# rev11.net
KiCad netlist of a schematic drawn in EAGLE
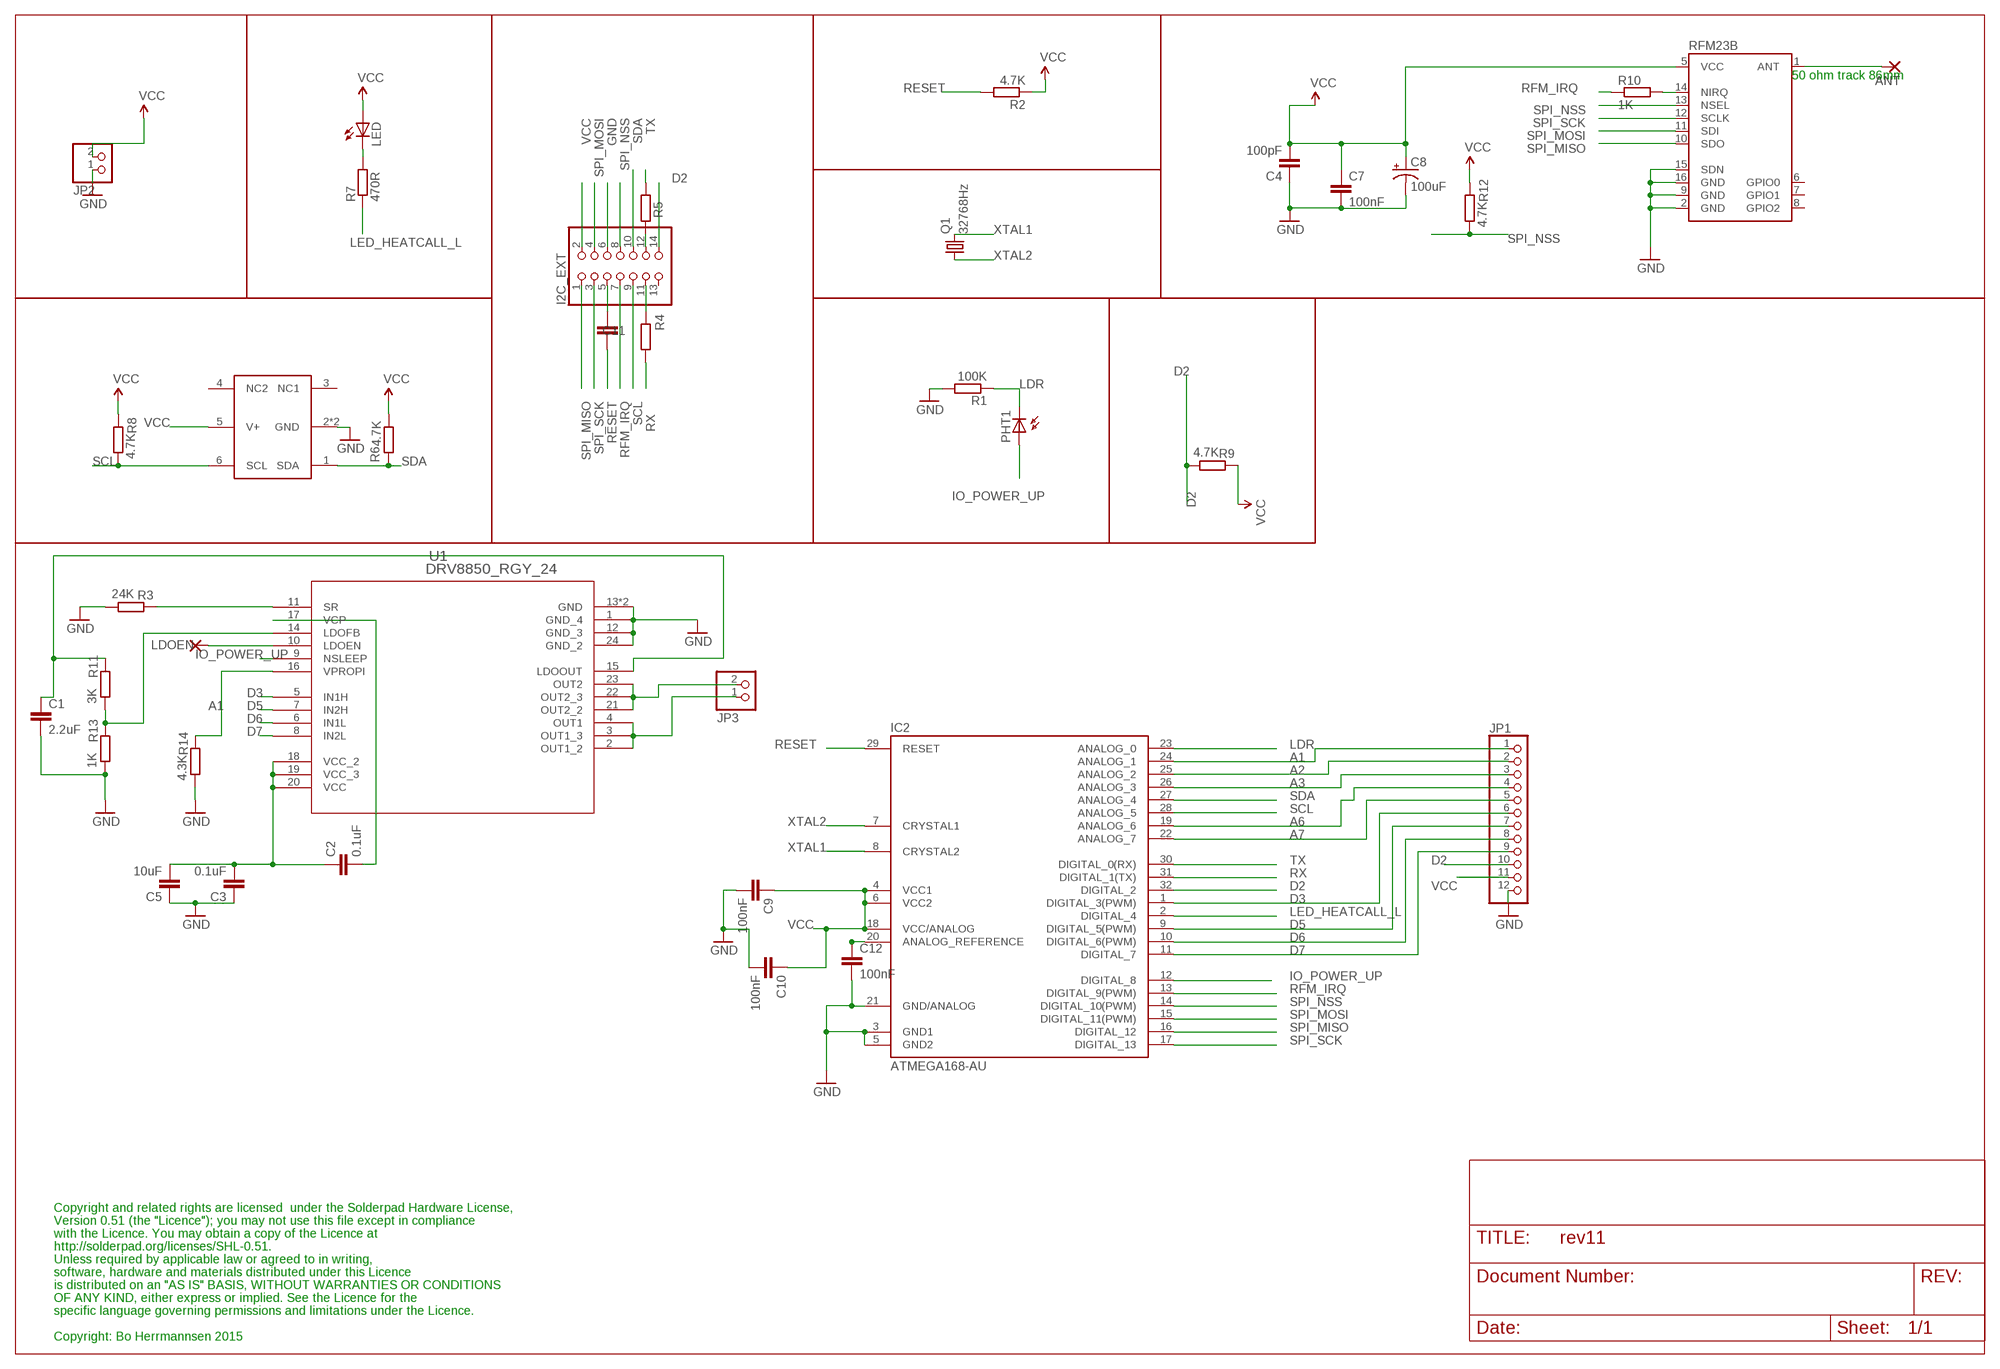
[diagram p0: schematic, sheet 1]

(export (version "E")
  (design (tool "Eeschema 10.0.6"))
  (components
    (comp (ref "ANT")
      (value "SMD2")
      (footprint "eagle-import:SMD1,27-2,54")
      (libsource (lib "eagle-import") (part "SMD2"))
    )
    (comp (ref "C1")
      (value "2.2uF")
      (footprint "eagle-import:C0603")
      (libsource (lib "eagle-import") (part "C-EUC0603"))
    )
    (comp (ref "C2")
      (value "0.1uF")
      (footprint "eagle-import:C0603")
      (libsource (lib "eagle-import") (part "C-EUC0603"))
    )
    (comp (ref "C3")
      (value "0.1uF")
      (footprint "eagle-import:C0603")
      (libsource (lib "eagle-import") (part "C-EUC0603"))
    )
    (comp (ref "C4")
      (value "100pF")
      (footprint "eagle-import:C0603")
      (libsource (lib "eagle-import") (part "C-EUC0603"))
    )
    (comp (ref "C5")
      (value "10uF")
      (footprint "eagle-import:C0603")
      (libsource (lib "eagle-import") (part "C-EUC0603"))
    )
    (comp (ref "C7")
      (value "100nF")
      (footprint "eagle-import:C0603")
      (libsource (lib "eagle-import") (part "C-EUC0603"))
    )
    (comp (ref "C8")
      (value "100uF")
      (footprint "eagle-import:EIA3216")
      (libsource (lib "eagle-import") (part "CAP_POL1206"))
    )
    (comp (ref "C9")
      (value "100nF")
      (footprint "eagle-import:C0603")
      (libsource (lib "eagle-import") (part "C-EUC0603"))
    )
    (comp (ref "C10")
      (value "100nF")
      (footprint "eagle-import:C0603")
      (libsource (lib "eagle-import") (part "C-EUC0603"))
    )
    (comp (ref "C11")
      (value "100nF")
      (footprint "eagle-import:C0603")
      (libsource (lib "eagle-import") (part "C-EUC0603"))
    )
    (comp (ref "C12")
      (value "100nF")
      (footprint "eagle-import:C0603")
      (libsource (lib "eagle-import") (part "C-EUC0603"))
    )
    (comp (ref "I2C_EXT")
      (value "PINHD-2X7")
      (footprint "eagle-import:2X07")
      (libsource (lib "eagle-import") (part "PINHD-2X7"))
    )
    (comp (ref "IC2")
      (value "ATMEGA168-AU")
      (footprint "eagle-import:TQFP32-08")
      (libsource (lib "eagle-import") (part "ATMEGA168-AU"))
    )
    (comp (ref "JP1")
      (value "PINHD-1X12")
      (footprint "eagle-import:1X12")
      (libsource (lib "eagle-import") (part "PINHD-1X12"))
    )
    (comp (ref "JP2")
      (value "PINHD-1X2")
      (footprint "eagle-import:1X02")
      (libsource (lib "eagle-import") (part "PINHD-1X2"))
    )
    (comp (ref "JP3")
      (value "PINHD-1X2")
      (footprint "eagle-import:1X02")
      (libsource (lib "eagle-import") (part "PINHD-1X2"))
    )
    (comp (ref "LDOEN")
      (value "WIREPAD2,15/1,0")
      (footprint "eagle-import:2,15_1,0")
      (libsource (lib "eagle-import") (part "WIREPAD2,15/1,0"))
    )
    (comp (ref "LED")
      (value "LEDCHIPLED_0603")
      (footprint "eagle-import:CHIPLED_0603")
      (libsource (lib "eagle-import") (part "LEDCHIPLED_0603"))
    )
    (comp (ref "PHT1")
      (value "BPX65")
      (footprint "eagle-import:BPX65")
      (fields (field (name "MPN") "BPX65."))
      (libsource (lib "eagle-import") (part "BPX65"))
    )
    (comp (ref "Q1")
      (value "32768Hz")
      (footprint "eagle-import:MC-306")
      (fields (field (name "MPN") "MC-306 60.0KHZ  100PPM ,12.5PF"))
      (libsource (lib "eagle-import") (part "MC-306"))
    )
    (comp (ref "R1")
      (value "100K")
      (footprint "eagle-import:R0603")
      (libsource (lib "eagle-import") (part "R-EU_R0603"))
    )
    (comp (ref "R2")
      (value "4.7K")
      (footprint "eagle-import:R0603")
      (libsource (lib "eagle-import") (part "R-EU_R0603"))
    )
    (comp (ref "R3")
      (value "24K")
      (footprint "eagle-import:R0603")
      (libsource (lib "eagle-import") (part "R-EU_R0603"))
    )
    (comp (ref "R4")
      (value "4.7K")
      (footprint "eagle-import:R0603")
      (libsource (lib "eagle-import") (part "R-EU_R0603"))
    )
    (comp (ref "R5")
      (value "4.7K")
      (footprint "eagle-import:R0603")
      (libsource (lib "eagle-import") (part "R-EU_R0603"))
    )
    (comp (ref "R6")
      (value "4.7K")
      (footprint "eagle-import:R0603")
      (libsource (lib "eagle-import") (part "R-EU_R0603"))
    )
    (comp (ref "R7")
      (value "470R")
      (footprint "eagle-import:R0603")
      (libsource (lib "eagle-import") (part "R-EU_R0603"))
    )
    (comp (ref "R8")
      (value "4.7K")
      (footprint "eagle-import:R0603")
      (libsource (lib "eagle-import") (part "R-EU_R0603"))
    )
    (comp (ref "R9")
      (value "4.7K")
      (footprint "eagle-import:R0603")
      (libsource (lib "eagle-import") (part "R-EU_R0603"))
    )
    (comp (ref "R10")
      (value "1K")
      (footprint "eagle-import:R0603")
      (libsource (lib "eagle-import") (part "R-EU_R0603"))
    )
    (comp (ref "R11")
      (value "3K")
      (footprint "eagle-import:R0603")
      (libsource (lib "eagle-import") (part "R-EU_R0603"))
    )
    (comp (ref "R12")
      (value "4.7K")
      (footprint "eagle-import:R0603")
      (libsource (lib "eagle-import") (part "R-EU_R0603"))
    )
    (comp (ref "R13")
      (value "1K")
      (footprint "eagle-import:R0603")
      (libsource (lib "eagle-import") (part "R-EU_R0603"))
    )
    (comp (ref "R14")
      (value "4.3K")
      (footprint "eagle-import:R0603")
      (libsource (lib "eagle-import") (part "R-EU_R0603"))
    )
    (comp (ref "RFM23B")
      (value "RFM23B")
      (footprint "eagle-import:RFM23-XXX-S1")
      (libsource (lib "eagle-import") (part "RFM23B"))
    )
    (comp (ref "U$4")
      (value "SHT21")
      (footprint "eagle-import:SHT21")
      (libsource (lib "eagle-import") (part "SHT21"))
    )
    (comp (ref "U1")
      (value "DRV8850_RGY_24")
      (footprint "eagle-import:RGY_24")
      (fields (field (name "MANUFACTURER_PART_NUMBER") "drv8850_rgy_24"))
      (libsource (lib "eagle-import") (part "DRV8850_RGY_24"))
    )
  )
  (nets
    (net (code "1") (name "/A1") (class "Default")
      (node (ref "IC2") (pin "24") (pinfunction "ANALOG_1_24") (pintype "bidirectional"))
      (node (ref "JP1") (pin "1") (pinfunction "1_1") (pintype "passive"))
      (node (ref "R14") (pin "2") (pinfunction "2_2") (pintype "passive"))
      (node (ref "U1") (pin "16") (pinfunction "VPROPI_16") (pintype "output"))
    )
    (net (code "2") (name "/A2") (class "Default")
      (node (ref "IC2") (pin "25") (pinfunction "ANALOG_2_25") (pintype "bidirectional"))
      (node (ref "JP1") (pin "2") (pinfunction "2_2") (pintype "passive"))
    )
    (net (code "3") (name "/A3") (class "Default")
      (node (ref "IC2") (pin "26") (pinfunction "ANALOG_3_26") (pintype "bidirectional"))
      (node (ref "JP1") (pin "3") (pinfunction "3_3") (pintype "passive"))
    )
    (net (code "4") (name "/A6") (class "Default")
      (node (ref "IC2") (pin "19") (pinfunction "ANALOG_6_19") (pintype "passive"))
      (node (ref "JP1") (pin "4") (pinfunction "4_4") (pintype "passive"))
    )
    (net (code "5") (name "/A7") (class "Default")
      (node (ref "IC2") (pin "22") (pinfunction "ANALOG_7_22") (pintype "passive"))
      (node (ref "JP1") (pin "5") (pinfunction "5_5") (pintype "passive"))
    )
    (net (code "6") (name "/D2") (class "Default")
      (node (ref "I2C_EXT") (pin "14") (pinfunction "14_14") (pintype "passive"))
      (node (ref "IC2") (pin "32") (pinfunction "DIGITAL_2_32") (pintype "bidirectional"))
      (node (ref "JP1") (pin "10") (pinfunction "10_10") (pintype "passive"))
      (node (ref "R9") (pin "1") (pinfunction "1_1") (pintype "passive"))
    )
    (net (code "7") (name "/D3") (class "Default")
      (node (ref "IC2") (pin "1") (pinfunction "DIGITAL_3(PWM)_1") (pintype "bidirectional"))
      (node (ref "JP1") (pin "6") (pinfunction "6_6") (pintype "passive"))
      (node (ref "U1") (pin "5") (pinfunction "IN1H_5") (pintype "input"))
    )
    (net (code "8") (name "/D5") (class "Default")
      (node (ref "IC2") (pin "9") (pinfunction "DIGITAL_5(PWM)_9") (pintype "bidirectional"))
      (node (ref "JP1") (pin "7") (pinfunction "7_7") (pintype "passive"))
      (node (ref "U1") (pin "7") (pinfunction "IN2H_7") (pintype "input"))
    )
    (net (code "9") (name "/D6") (class "Default")
      (node (ref "IC2") (pin "10") (pinfunction "DIGITAL_6(PWM)_10") (pintype "bidirectional"))
      (node (ref "JP1") (pin "8") (pinfunction "8_8") (pintype "passive"))
      (node (ref "U1") (pin "6") (pinfunction "IN1L_6") (pintype "input"))
    )
    (net (code "10") (name "/D7") (class "Default")
      (node (ref "IC2") (pin "11") (pinfunction "DIGITAL_7_11") (pintype "bidirectional"))
      (node (ref "JP1") (pin "9") (pinfunction "9_9") (pintype "passive"))
      (node (ref "U1") (pin "8") (pinfunction "IN2L_8") (pintype "input"))
    )
    (net (code "11") (name "/IO_POWER_UP") (class "Default")
      (node (ref "IC2") (pin "12") (pinfunction "DIGITAL_8_12") (pintype "bidirectional"))
      (node (ref "PHT1") (pin "A") (pinfunction "A_A") (pintype "passive"))
      (node (ref "U1") (pin "9") (pinfunction "NSLEEP_9") (pintype "input"))
    )
    (net (code "12") (name "/LDR") (class "Default")
      (node (ref "IC2") (pin "23") (pinfunction "ANALOG_0_23") (pintype "bidirectional"))
      (node (ref "PHT1") (pin "K") (pinfunction "C_K") (pintype "passive"))
      (node (ref "R1") (pin "1") (pinfunction "1_1") (pintype "passive"))
    )
    (net (code "13") (name "/LED_HEATCALL_L") (class "Default")
      (node (ref "IC2") (pin "2") (pinfunction "DIGITAL_4_2") (pintype "bidirectional"))
      (node (ref "R7") (pin "1") (pinfunction "1_1") (pintype "passive"))
    )
    (net (code "14") (name "/RESET") (class "Default")
      (node (ref "C11") (pin "1") (pinfunction "1_1") (pintype "passive"))
      (node (ref "IC2") (pin "29") (pinfunction "RESET_29") (pintype "bidirectional"))
      (node (ref "R2") (pin "2") (pinfunction "2_2") (pintype "passive"))
    )
    (net (code "15") (name "/RFM_IRQ") (class "Default")
      (node (ref "I2C_EXT") (pin "7") (pinfunction "7_7") (pintype "passive"))
      (node (ref "IC2") (pin "13") (pinfunction "DIGITAL_9(PWM)_13") (pintype "bidirectional"))
      (node (ref "R10") (pin "1") (pinfunction "1_1") (pintype "passive"))
    )
    (net (code "16") (name "/RX") (class "Default")
      (node (ref "IC2") (pin "31") (pinfunction "DIGITAL_1(TX)_31") (pintype "bidirectional"))
      (node (ref "R4") (pin "1") (pinfunction "1_1") (pintype "passive"))
    )
    (net (code "17") (name "/SCL") (class "Default")
      (node (ref "I2C_EXT") (pin "9") (pinfunction "9_9") (pintype "passive"))
      (node (ref "IC2") (pin "28") (pinfunction "ANALOG_5_28") (pintype "bidirectional"))
      (node (ref "R8") (pin "1") (pinfunction "1_1") (pintype "passive"))
      (node (ref "U$4") (pin "6") (pinfunction "SCL_6") (pintype "bidirectional"))
    )
    (net (code "18") (name "/SDA") (class "Default")
      (node (ref "I2C_EXT") (pin "10") (pinfunction "10_10") (pintype "passive"))
      (node (ref "IC2") (pin "27") (pinfunction "ANALOG_4_27") (pintype "bidirectional"))
      (node (ref "R6") (pin "2") (pinfunction "2_2") (pintype "passive"))
      (node (ref "U$4") (pin "1") (pinfunction "SDA_1") (pintype "bidirectional"))
    )
    (net (code "19") (name "/SPI_MISO") (class "Default")
      (node (ref "I2C_EXT") (pin "1") (pinfunction "1_1") (pintype "passive"))
      (node (ref "IC2") (pin "16") (pinfunction "DIGITAL_12_16") (pintype "bidirectional"))
      (node (ref "RFM23B") (pin "10") (pinfunction "SDO_10") (pintype "output"))
    )
    (net (code "20") (name "/SPI_MOSI") (class "Default")
      (node (ref "I2C_EXT") (pin "4") (pinfunction "4_4") (pintype "passive"))
      (node (ref "IC2") (pin "15") (pinfunction "DIGITAL_11(PWM)_15") (pintype "bidirectional"))
      (node (ref "RFM23B") (pin "11") (pinfunction "SDI_11") (pintype "input"))
    )
    (net (code "21") (name "/SPI_NSS") (class "Default")
      (node (ref "I2C_EXT") (pin "8") (pinfunction "8_8") (pintype "passive"))
      (node (ref "IC2") (pin "14") (pinfunction "DIGITAL_10(PWM)_14") (pintype "bidirectional"))
      (node (ref "R12") (pin "1") (pinfunction "1_1") (pintype "passive"))
      (node (ref "RFM23B") (pin "13") (pinfunction "NSEL_13") (pintype "input"))
    )
    (net (code "22") (name "/SPI_SCK") (class "Default")
      (node (ref "I2C_EXT") (pin "3") (pinfunction "3_3") (pintype "passive"))
      (node (ref "IC2") (pin "17") (pinfunction "DIGITAL_13_17") (pintype "bidirectional"))
      (node (ref "RFM23B") (pin "12") (pinfunction "SCLK_12") (pintype "input"))
    )
    (net (code "23") (name "/TX") (class "Default")
      (node (ref "IC2") (pin "30") (pinfunction "DIGITAL_0(RX)_30") (pintype "bidirectional"))
      (node (ref "R5") (pin "1") (pinfunction "1_1") (pintype "passive"))
    )
    (net (code "24") (name "/XTAL1") (class "Default")
      (node (ref "IC2") (pin "8") (pinfunction "CRYSTAL2_8") (pintype "bidirectional"))
      (node (ref "Q1") (pin "4") (pinfunction "2_4") (pintype "passive"))
    )
    (net (code "25") (name "/XTAL2") (class "Default")
      (node (ref "IC2") (pin "7") (pinfunction "CRYSTAL1_7") (pintype "bidirectional"))
      (node (ref "Q1") (pin "1") (pinfunction "1_1") (pintype "passive"))
    )
    (net (code "26") (name "GND") (class "Default")
      (node (ref "C1") (pin "2") (pinfunction "2_2") (pintype "passive"))
      (node (ref "C10") (pin "2") (pinfunction "2_2") (pintype "passive"))
      (node (ref "C12") (pin "2") (pinfunction "2_2") (pintype "passive"))
      (node (ref "C3") (pin "1") (pinfunction "1_1") (pintype "passive"))
      (node (ref "C4") (pin "1") (pinfunction "1_1") (pintype "passive"))
      (node (ref "C5") (pin "1") (pinfunction "1_1") (pintype "passive"))
      (node (ref "C7") (pin "2") (pinfunction "2_2") (pintype "passive"))
      (node (ref "C8") (pin "C") (pinfunction "-_C") (pintype "passive"))
      (node (ref "C9") (pin "2") (pinfunction "2_2") (pintype "passive"))
      (node (ref "I2C_EXT") (pin "6") (pinfunction "6_6") (pintype "passive"))
      (node (ref "IC2") (pin "21") (pinfunction "GND/ANALOG_21") (pintype "power_in"))
      (node (ref "IC2") (pin "3") (pinfunction "GND1_3") (pintype "power_in"))
      (node (ref "IC2") (pin "5") (pinfunction "GND2_5") (pintype "power_in"))
      (node (ref "JP1") (pin "12") (pinfunction "12_12") (pintype "passive"))
      (node (ref "JP2") (pin "1") (pinfunction "1_1") (pintype "passive"))
      (node (ref "R1") (pin "2") (pinfunction "2_2") (pintype "passive"))
      (node (ref "R13") (pin "1") (pinfunction "1_1") (pintype "passive"))
      (node (ref "R14") (pin "1") (pinfunction "1_1") (pintype "passive"))
      (node (ref "R3") (pin "1") (pinfunction "1_1") (pintype "passive"))
      (node (ref "RFM23B") (pin "15") (pinfunction "SDN_15") (pintype "input"))
      (node (ref "RFM23B") (pin "16") (pinfunction "GND_16") (pintype "power_in"))
      (node (ref "RFM23B") (pin "2") (pinfunction "GND_2") (pintype "power_in"))
      (node (ref "RFM23B") (pin "9") (pinfunction "GND_9") (pintype "power_in"))
      (node (ref "U$4") (pin "2") (pinfunction "GND_2") (pintype "bidirectional"))
      (node (ref "U$4") (pin "P$1") (pinfunction "GND_P$1") (pintype "bidirectional"))
      (node (ref "U1") (pin "1") (pinfunction "GND_4_1") (pintype "power_in"))
      (node (ref "U1") (pin "12") (pinfunction "GND_3_12") (pintype "power_in"))
      (node (ref "U1") (pin "13") (pinfunction "GND_13") (pintype "power_in"))
      (node (ref "U1") (pin "24") (pinfunction "GND_2_24") (pintype "power_in"))
      (node (ref "U1") (pin "25") (pinfunction "GND_25") (pintype "power_in"))
    )
    (net (code "27") (name "Net-(ANT-P)") (class "Default")
      (node (ref "ANT") (pin "1") (pinfunction "P_1") (pintype "passive"))
      (node (ref "RFM23B") (pin "1") (pinfunction "ANT_1") (pintype "bidirectional"))
    )
    (net (code "28") (name "Net-(C11-Pad2)") (class "Default")
      (node (ref "C11") (pin "2") (pinfunction "2_2") (pintype "passive"))
      (node (ref "I2C_EXT") (pin "5") (pinfunction "5_5") (pintype "passive"))
    )
    (net (code "29") (name "Net-(I2C_EXT-Pad11)") (class "Default")
      (node (ref "I2C_EXT") (pin "11") (pinfunction "11_11") (pintype "passive"))
      (node (ref "R4") (pin "2") (pinfunction "2_2") (pintype "passive"))
    )
    (net (code "30") (name "Net-(I2C_EXT-Pad12)") (class "Default")
      (node (ref "I2C_EXT") (pin "12") (pinfunction "12_12") (pintype "passive"))
      (node (ref "R5") (pin "2") (pinfunction "2_2") (pintype "passive"))
    )
    (net (code "31") (name "Net-(IC2-ANALOG_REFERENCE)") (class "Default")
      (node (ref "C12") (pin "1") (pinfunction "1_1") (pintype "passive"))
      (node (ref "IC2") (pin "20") (pinfunction "ANALOG_REFERENCE_20") (pintype "passive"))
    )
    (net (code "32") (name "Net-(LDOEN-P)") (class "Default")
      (node (ref "LDOEN") (pin "1") (pinfunction "P_1") (pintype "passive"))
      (node (ref "U1") (pin "10") (pinfunction "LDOEN_10") (pintype "input"))
    )
    (net (code "33") (name "Net-(LED-PadC)") (class "Default")
      (node (ref "LED") (pin "C") (pinfunction "C_C") (pintype "passive"))
      (node (ref "R7") (pin "2") (pinfunction "2_2") (pintype "passive"))
    )
    (net (code "34") (name "Net-(RFM23B-NIRQ)") (class "Default")
      (node (ref "R10") (pin "2") (pinfunction "2_2") (pintype "passive"))
      (node (ref "RFM23B") (pin "14") (pinfunction "NIRQ_14") (pintype "output"))
    )
    (net (code "35") (name "Net-(U1-LDOFB)") (class "Default")
      (node (ref "R11") (pin "1") (pinfunction "1_1") (pintype "passive"))
      (node (ref "R13") (pin "2") (pinfunction "2_2") (pintype "passive"))
      (node (ref "U1") (pin "14") (pinfunction "LDOFB_14") (pintype "input"))
    )
    (net (code "36") (name "Net-(U1-LDOOUT)") (class "Default")
      (node (ref "C1") (pin "1") (pinfunction "1_1") (pintype "passive"))
      (node (ref "R11") (pin "2") (pinfunction "2_2") (pintype "passive"))
      (node (ref "U1") (pin "15") (pinfunction "LDOOUT_15") (pintype "output"))
    )
    (net (code "37") (name "Net-(U1-OUT1)") (class "Default")
      (node (ref "JP3") (pin "1") (pinfunction "1_1") (pintype "passive"))
      (node (ref "U1") (pin "2") (pinfunction "OUT1_2_2") (pintype "output"))
      (node (ref "U1") (pin "3") (pinfunction "OUT1_3_3") (pintype "output"))
      (node (ref "U1") (pin "4") (pinfunction "OUT1_4") (pintype "output"))
    )
    (net (code "38") (name "Net-(U1-OUT2)") (class "Default")
      (node (ref "JP3") (pin "2") (pinfunction "2_2") (pintype "passive"))
      (node (ref "U1") (pin "21") (pinfunction "OUT2_2_21") (pintype "output"))
      (node (ref "U1") (pin "22") (pinfunction "OUT2_3_22") (pintype "output"))
      (node (ref "U1") (pin "23") (pinfunction "OUT2_23") (pintype "output"))
    )
    (net (code "39") (name "Net-(U1-SR)") (class "Default")
      (node (ref "R3") (pin "2") (pinfunction "2_2") (pintype "passive"))
      (node (ref "U1") (pin "11") (pinfunction "SR_11") (pintype "bidirectional"))
    )
    (net (code "40") (name "Net-(U1-VCP)") (class "Default")
      (node (ref "C2") (pin "2") (pinfunction "2_2") (pintype "passive"))
      (node (ref "U1") (pin "17") (pinfunction "VCP_17") (pintype "passive"))
    )
    (net (code "41") (name "VCC") (class "Default")
      (node (ref "C10") (pin "1") (pinfunction "1_1") (pintype "passive"))
      (node (ref "C2") (pin "1") (pinfunction "1_1") (pintype "passive"))
      (node (ref "C3") (pin "2") (pinfunction "2_2") (pintype "passive"))
      (node (ref "C4") (pin "2") (pinfunction "2_2") (pintype "passive"))
      (node (ref "C5") (pin "2") (pinfunction "2_2") (pintype "passive"))
      (node (ref "C7") (pin "1") (pinfunction "1_1") (pintype "passive"))
      (node (ref "C8") (pin "A") (pinfunction "+_A") (pintype "passive"))
      (node (ref "C9") (pin "1") (pinfunction "1_1") (pintype "passive"))
      (node (ref "I2C_EXT") (pin "2") (pinfunction "2_2") (pintype "passive"))
      (node (ref "IC2") (pin "18") (pinfunction "VCC/ANALOG_18") (pintype "passive"))
      (node (ref "IC2") (pin "4") (pinfunction "VCC1_4") (pintype "power_in"))
      (node (ref "IC2") (pin "6") (pinfunction "VCC2_6") (pintype "power_in"))
      (node (ref "JP1") (pin "11") (pinfunction "11_11") (pintype "passive"))
      (node (ref "JP2") (pin "2") (pinfunction "2_2") (pintype "passive"))
      (node (ref "LED") (pin "A") (pinfunction "A_A") (pintype "passive"))
      (node (ref "R12") (pin "2") (pinfunction "2_2") (pintype "passive"))
      (node (ref "R2") (pin "1") (pinfunction "1_1") (pintype "passive"))
      (node (ref "R6") (pin "1") (pinfunction "1_1") (pintype "passive"))
      (node (ref "R8") (pin "2") (pinfunction "2_2") (pintype "passive"))
      (node (ref "R9") (pin "2") (pinfunction "2_2") (pintype "passive"))
      (node (ref "RFM23B") (pin "5") (pinfunction "VCC_5") (pintype "bidirectional"))
      (node (ref "U$4") (pin "5") (pinfunction "V+_5") (pintype "bidirectional"))
      (node (ref "U1") (pin "18") (pinfunction "VCC_2_18") (pintype "power_in"))
      (node (ref "U1") (pin "19") (pinfunction "VCC_3_19") (pintype "power_in"))
      (node (ref "U1") (pin "20") (pinfunction "VCC_20") (pintype "power_in"))
    )
    (net (code "42") (name "unconnected-(I2C_EXT-Pad13)") (class "Default")
      (node (ref "I2C_EXT") (pin "13") (pinfunction "13_13") (pintype "passive"))
    )
    (net (code "43") (name "unconnected-(RFM23B-GPIO0-Pad6)") (class "Default")
      (node (ref "RFM23B") (pin "6") (pinfunction "GPIO0_6") (pintype "bidirectional"))
    )
    (net (code "44") (name "unconnected-(RFM23B-GPIO1-Pad7)") (class "Default")
      (node (ref "RFM23B") (pin "7") (pinfunction "GPIO1_7") (pintype "bidirectional"))
    )
    (net (code "45") (name "unconnected-(RFM23B-GPIO2-Pad8)") (class "Default")
      (node (ref "RFM23B") (pin "8") (pinfunction "GPIO2_8") (pintype "bidirectional"))
    )
    (net (code "46") (name "unconnected-(U$4-NC1-Pad3)") (class "Default")
      (node (ref "U$4") (pin "3") (pinfunction "NC1_3") (pintype "bidirectional"))
    )
    (net (code "47") (name "unconnected-(U$4-NC2-Pad4)") (class "Default")
      (node (ref "U$4") (pin "4") (pinfunction "NC2_4") (pintype "bidirectional"))
    )
  )
)
